# WS2812_MATRIX_7.net
KiCad netlist of a schematic drawn in Altium Designer
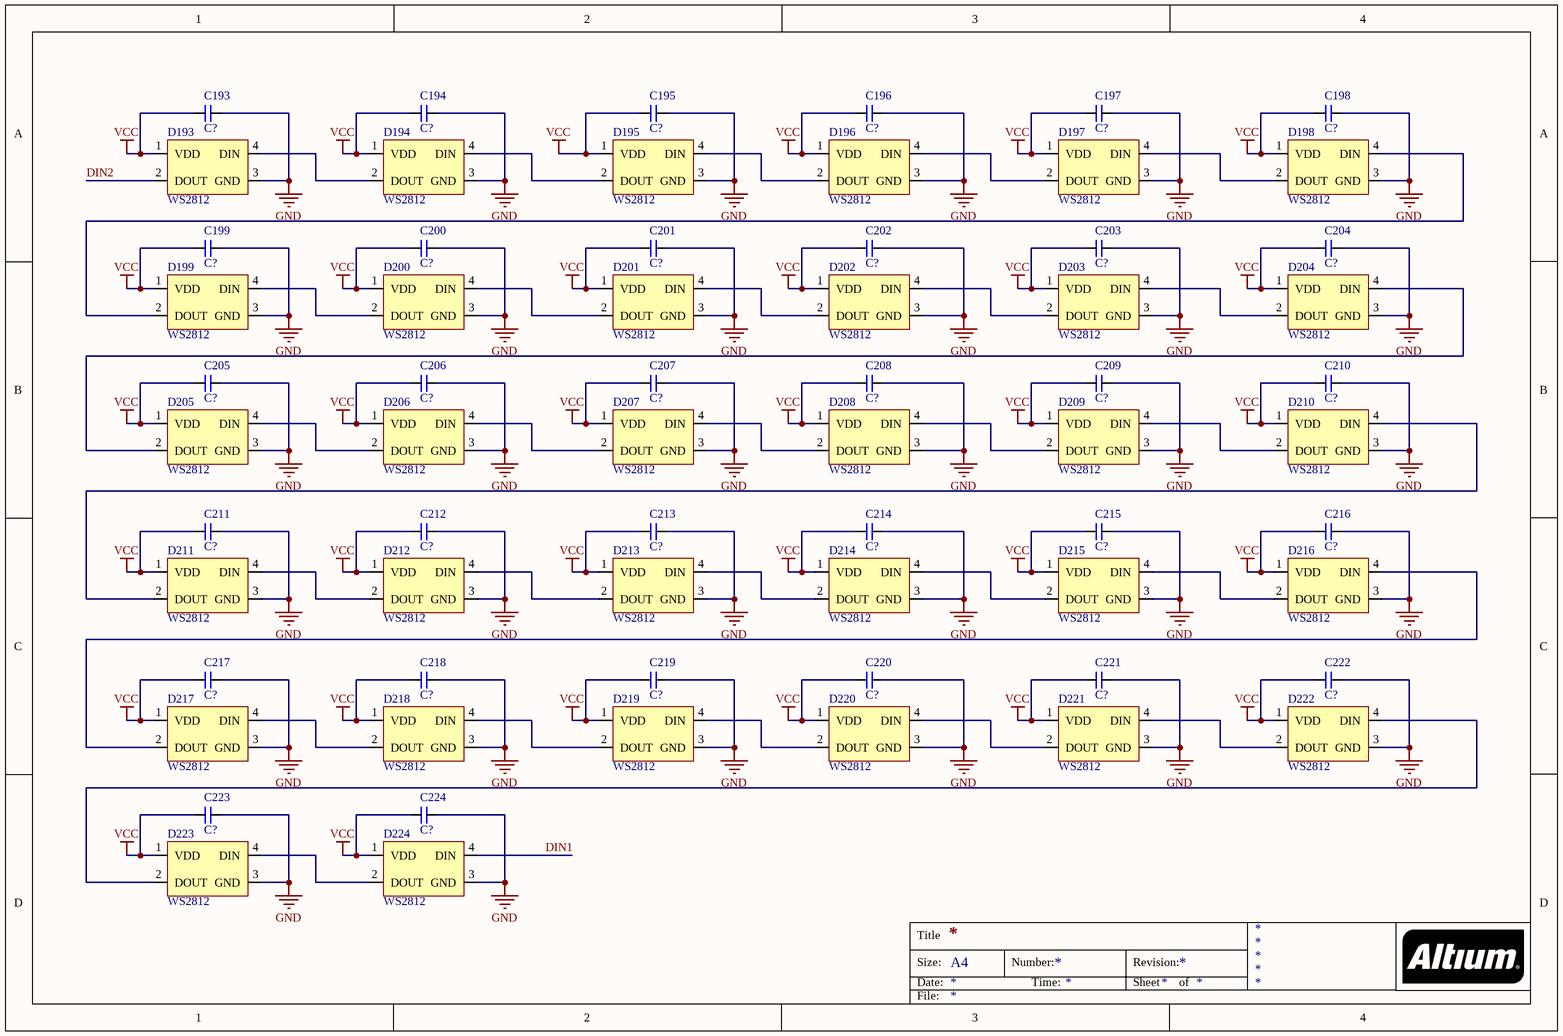
[diagram p0: WS2812_MATRIX_7.SchDoc]

(export (version "E")
  (design (tool "Eeschema 10.0.6"))
  (components
    (comp (ref "C193")
      (value "C?")
      (footprint "C0603")
      (description "Cap")
      (libsource (lib "SCH_Bacsic") (part "CAP"))
    )
    (comp (ref "C194")
      (value "C?")
      (footprint "C0603")
      (description "Cap")
      (libsource (lib "SCH_Bacsic") (part "CAP"))
    )
    (comp (ref "C195")
      (value "C?")
      (footprint "C0603")
      (description "Cap")
      (libsource (lib "SCH_Bacsic") (part "CAP"))
    )
    (comp (ref "C196")
      (value "C?")
      (footprint "C0603")
      (description "Cap")
      (libsource (lib "SCH_Bacsic") (part "CAP"))
    )
    (comp (ref "C197")
      (value "C?")
      (footprint "C0603")
      (description "Cap")
      (libsource (lib "SCH_Bacsic") (part "CAP"))
    )
    (comp (ref "C198")
      (value "C?")
      (footprint "C0603")
      (description "Cap")
      (libsource (lib "SCH_Bacsic") (part "CAP"))
    )
    (comp (ref "C199")
      (value "C?")
      (footprint "C0603")
      (description "Cap")
      (libsource (lib "SCH_Bacsic") (part "CAP"))
    )
    (comp (ref "C200")
      (value "C?")
      (footprint "C0603")
      (description "Cap")
      (libsource (lib "SCH_Bacsic") (part "CAP"))
    )
    (comp (ref "C201")
      (value "C?")
      (footprint "C0603")
      (description "Cap")
      (libsource (lib "SCH_Bacsic") (part "CAP"))
    )
    (comp (ref "C202")
      (value "C?")
      (footprint "C0603")
      (description "Cap")
      (libsource (lib "SCH_Bacsic") (part "CAP"))
    )
    (comp (ref "C203")
      (value "C?")
      (footprint "C0603")
      (description "Cap")
      (libsource (lib "SCH_Bacsic") (part "CAP"))
    )
    (comp (ref "C204")
      (value "C?")
      (footprint "C0603")
      (description "Cap")
      (libsource (lib "SCH_Bacsic") (part "CAP"))
    )
    (comp (ref "C205")
      (value "C?")
      (footprint "C0603")
      (description "Cap")
      (libsource (lib "SCH_Bacsic") (part "CAP"))
    )
    (comp (ref "C206")
      (value "C?")
      (footprint "C0603")
      (description "Cap")
      (libsource (lib "SCH_Bacsic") (part "CAP"))
    )
    (comp (ref "C207")
      (value "C?")
      (footprint "C0603")
      (description "Cap")
      (libsource (lib "SCH_Bacsic") (part "CAP"))
    )
    (comp (ref "C208")
      (value "C?")
      (footprint "C0603")
      (description "Cap")
      (libsource (lib "SCH_Bacsic") (part "CAP"))
    )
    (comp (ref "C209")
      (value "C?")
      (footprint "C0603")
      (description "Cap")
      (libsource (lib "SCH_Bacsic") (part "CAP"))
    )
    (comp (ref "C210")
      (value "C?")
      (footprint "C0603")
      (description "Cap")
      (libsource (lib "SCH_Bacsic") (part "CAP"))
    )
    (comp (ref "C211")
      (value "C?")
      (footprint "C0603")
      (description "Cap")
      (libsource (lib "SCH_Bacsic") (part "CAP"))
    )
    (comp (ref "C212")
      (value "C?")
      (footprint "C0603")
      (description "Cap")
      (libsource (lib "SCH_Bacsic") (part "CAP"))
    )
    (comp (ref "C213")
      (value "C?")
      (footprint "C0603")
      (description "Cap")
      (libsource (lib "SCH_Bacsic") (part "CAP"))
    )
    (comp (ref "C214")
      (value "C?")
      (footprint "C0603")
      (description "Cap")
      (libsource (lib "SCH_Bacsic") (part "CAP"))
    )
    (comp (ref "C215")
      (value "C?")
      (footprint "C0603")
      (description "Cap")
      (libsource (lib "SCH_Bacsic") (part "CAP"))
    )
    (comp (ref "C216")
      (value "C?")
      (footprint "C0603")
      (description "Cap")
      (libsource (lib "SCH_Bacsic") (part "CAP"))
    )
    (comp (ref "C217")
      (value "C?")
      (footprint "C0603")
      (description "Cap")
      (libsource (lib "SCH_Bacsic") (part "CAP"))
    )
    (comp (ref "C218")
      (value "C?")
      (footprint "C0603")
      (description "Cap")
      (libsource (lib "SCH_Bacsic") (part "CAP"))
    )
    (comp (ref "C219")
      (value "C?")
      (footprint "C0603")
      (description "Cap")
      (libsource (lib "SCH_Bacsic") (part "CAP"))
    )
    (comp (ref "C220")
      (value "C?")
      (footprint "C0603")
      (description "Cap")
      (libsource (lib "SCH_Bacsic") (part "CAP"))
    )
    (comp (ref "C221")
      (value "C?")
      (footprint "C0603")
      (description "Cap")
      (libsource (lib "SCH_Bacsic") (part "CAP"))
    )
    (comp (ref "C222")
      (value "C?")
      (footprint "C0603")
      (description "Cap")
      (libsource (lib "SCH_Bacsic") (part "CAP"))
    )
    (comp (ref "C223")
      (value "C?")
      (footprint "C0603")
      (description "Cap")
      (libsource (lib "SCH_Bacsic") (part "CAP"))
    )
    (comp (ref "C224")
      (value "C?")
      (footprint "C0603")
      (description "Cap")
      (libsource (lib "SCH_Bacsic") (part "CAP"))
    )
    (comp (ref "D193")
      (value "WS2812")
      (footprint "WS2812_3528")
      (libsource (lib "SCH_Bacsic") (part "WS2812"))
    )
    (comp (ref "D194")
      (value "WS2812")
      (footprint "WS2812_3528")
      (libsource (lib "SCH_Bacsic") (part "WS2812"))
    )
    (comp (ref "D195")
      (value "WS2812")
      (footprint "WS2812_3528")
      (libsource (lib "SCH_Bacsic") (part "WS2812"))
    )
    (comp (ref "D196")
      (value "WS2812")
      (footprint "WS2812_3528")
      (libsource (lib "SCH_Bacsic") (part "WS2812"))
    )
    (comp (ref "D197")
      (value "WS2812")
      (footprint "WS2812_3528")
      (libsource (lib "SCH_Bacsic") (part "WS2812"))
    )
    (comp (ref "D198")
      (value "WS2812")
      (footprint "WS2812_3528")
      (libsource (lib "SCH_Bacsic") (part "WS2812"))
    )
    (comp (ref "D199")
      (value "WS2812")
      (footprint "WS2812_3528")
      (libsource (lib "SCH_Bacsic") (part "WS2812"))
    )
    (comp (ref "D200")
      (value "WS2812")
      (footprint "WS2812_3528")
      (libsource (lib "SCH_Bacsic") (part "WS2812"))
    )
    (comp (ref "D201")
      (value "WS2812")
      (footprint "WS2812_3528")
      (libsource (lib "SCH_Bacsic") (part "WS2812"))
    )
    (comp (ref "D202")
      (value "WS2812")
      (footprint "WS2812_3528")
      (libsource (lib "SCH_Bacsic") (part "WS2812"))
    )
    (comp (ref "D203")
      (value "WS2812")
      (footprint "WS2812_3528")
      (libsource (lib "SCH_Bacsic") (part "WS2812"))
    )
    (comp (ref "D204")
      (value "WS2812")
      (footprint "WS2812_3528")
      (libsource (lib "SCH_Bacsic") (part "WS2812"))
    )
    (comp (ref "D205")
      (value "WS2812")
      (footprint "WS2812_3528")
      (libsource (lib "SCH_Bacsic") (part "WS2812"))
    )
    (comp (ref "D206")
      (value "WS2812")
      (footprint "WS2812_3528")
      (libsource (lib "SCH_Bacsic") (part "WS2812"))
    )
    (comp (ref "D207")
      (value "WS2812")
      (footprint "WS2812_3528")
      (libsource (lib "SCH_Bacsic") (part "WS2812"))
    )
    (comp (ref "D208")
      (value "WS2812")
      (footprint "WS2812_3528")
      (libsource (lib "SCH_Bacsic") (part "WS2812"))
    )
    (comp (ref "D209")
      (value "WS2812")
      (footprint "WS2812_3528")
      (libsource (lib "SCH_Bacsic") (part "WS2812"))
    )
    (comp (ref "D210")
      (value "WS2812")
      (footprint "WS2812_3528")
      (libsource (lib "SCH_Bacsic") (part "WS2812"))
    )
    (comp (ref "D211")
      (value "WS2812")
      (footprint "WS2812_3528")
      (libsource (lib "SCH_Bacsic") (part "WS2812"))
    )
    (comp (ref "D212")
      (value "WS2812")
      (footprint "WS2812_3528")
      (libsource (lib "SCH_Bacsic") (part "WS2812"))
    )
    (comp (ref "D213")
      (value "WS2812")
      (footprint "WS2812_3528")
      (libsource (lib "SCH_Bacsic") (part "WS2812"))
    )
    (comp (ref "D214")
      (value "WS2812")
      (footprint "WS2812_3528")
      (libsource (lib "SCH_Bacsic") (part "WS2812"))
    )
    (comp (ref "D215")
      (value "WS2812")
      (footprint "WS2812_3528")
      (libsource (lib "SCH_Bacsic") (part "WS2812"))
    )
    (comp (ref "D216")
      (value "WS2812")
      (footprint "WS2812_3528")
      (libsource (lib "SCH_Bacsic") (part "WS2812"))
    )
    (comp (ref "D217")
      (value "WS2812")
      (footprint "WS2812_3528")
      (libsource (lib "SCH_Bacsic") (part "WS2812"))
    )
    (comp (ref "D218")
      (value "WS2812")
      (footprint "WS2812_3528")
      (libsource (lib "SCH_Bacsic") (part "WS2812"))
    )
    (comp (ref "D219")
      (value "WS2812")
      (footprint "WS2812_3528")
      (libsource (lib "SCH_Bacsic") (part "WS2812"))
    )
    (comp (ref "D220")
      (value "WS2812")
      (footprint "WS2812_3528")
      (libsource (lib "SCH_Bacsic") (part "WS2812"))
    )
    (comp (ref "D221")
      (value "WS2812")
      (footprint "WS2812_3528")
      (libsource (lib "SCH_Bacsic") (part "WS2812"))
    )
    (comp (ref "D222")
      (value "WS2812")
      (footprint "WS2812_3528")
      (libsource (lib "SCH_Bacsic") (part "WS2812"))
    )
    (comp (ref "D223")
      (value "WS2812")
      (footprint "WS2812_3528")
      (libsource (lib "SCH_Bacsic") (part "WS2812"))
    )
    (comp (ref "D224")
      (value "WS2812")
      (footprint "WS2812_3528")
      (libsource (lib "SCH_Bacsic") (part "WS2812"))
    )
  )
  (nets
    (net (code "1") (name "/DIN1") (class "Default")
      (node (ref "D224") (pin "4") (pinfunction "DIN_4") (pintype "passive"))
    )
    (net (code "2") (name "/DIN2") (class "Default")
      (node (ref "D193") (pin "2") (pinfunction "DOUT_2") (pintype "passive"))
    )
    (net (code "3") (name "GND") (class "Default")
      (node (ref "C193") (pin "2") (pintype "passive"))
      (node (ref "C194") (pin "2") (pintype "passive"))
      (node (ref "C195") (pin "2") (pintype "passive"))
      (node (ref "C196") (pin "2") (pintype "passive"))
      (node (ref "C197") (pin "2") (pintype "passive"))
      (node (ref "C198") (pin "2") (pintype "passive"))
      (node (ref "C199") (pin "2") (pintype "passive"))
      (node (ref "C200") (pin "2") (pintype "passive"))
      (node (ref "C201") (pin "2") (pintype "passive"))
      (node (ref "C202") (pin "2") (pintype "passive"))
      (node (ref "C203") (pin "2") (pintype "passive"))
      (node (ref "C204") (pin "2") (pintype "passive"))
      (node (ref "C205") (pin "2") (pintype "passive"))
      (node (ref "C206") (pin "2") (pintype "passive"))
      (node (ref "C207") (pin "2") (pintype "passive"))
      (node (ref "C208") (pin "2") (pintype "passive"))
      (node (ref "C209") (pin "2") (pintype "passive"))
      (node (ref "C210") (pin "2") (pintype "passive"))
      (node (ref "C211") (pin "2") (pintype "passive"))
      (node (ref "C212") (pin "2") (pintype "passive"))
      (node (ref "C213") (pin "2") (pintype "passive"))
      (node (ref "C214") (pin "2") (pintype "passive"))
      (node (ref "C215") (pin "2") (pintype "passive"))
      (node (ref "C216") (pin "2") (pintype "passive"))
      (node (ref "C217") (pin "2") (pintype "passive"))
      (node (ref "C218") (pin "2") (pintype "passive"))
      (node (ref "C219") (pin "2") (pintype "passive"))
      (node (ref "C220") (pin "2") (pintype "passive"))
      (node (ref "C221") (pin "2") (pintype "passive"))
      (node (ref "C222") (pin "2") (pintype "passive"))
      (node (ref "C223") (pin "2") (pintype "passive"))
      (node (ref "C224") (pin "2") (pintype "passive"))
      (node (ref "D193") (pin "3") (pinfunction "GND_3") (pintype "passive"))
      (node (ref "D194") (pin "3") (pinfunction "GND_3") (pintype "passive"))
      (node (ref "D195") (pin "3") (pinfunction "GND_3") (pintype "passive"))
      (node (ref "D196") (pin "3") (pinfunction "GND_3") (pintype "passive"))
      (node (ref "D197") (pin "3") (pinfunction "GND_3") (pintype "passive"))
      (node (ref "D198") (pin "3") (pinfunction "GND_3") (pintype "passive"))
      (node (ref "D199") (pin "3") (pinfunction "GND_3") (pintype "passive"))
      (node (ref "D200") (pin "3") (pinfunction "GND_3") (pintype "passive"))
      (node (ref "D201") (pin "3") (pinfunction "GND_3") (pintype "passive"))
      (node (ref "D202") (pin "3") (pinfunction "GND_3") (pintype "passive"))
      (node (ref "D203") (pin "3") (pinfunction "GND_3") (pintype "passive"))
      (node (ref "D204") (pin "3") (pinfunction "GND_3") (pintype "passive"))
      (node (ref "D205") (pin "3") (pinfunction "GND_3") (pintype "passive"))
      (node (ref "D206") (pin "3") (pinfunction "GND_3") (pintype "passive"))
      (node (ref "D207") (pin "3") (pinfunction "GND_3") (pintype "passive"))
      (node (ref "D208") (pin "3") (pinfunction "GND_3") (pintype "passive"))
      (node (ref "D209") (pin "3") (pinfunction "GND_3") (pintype "passive"))
      (node (ref "D210") (pin "3") (pinfunction "GND_3") (pintype "passive"))
      (node (ref "D211") (pin "3") (pinfunction "GND_3") (pintype "passive"))
      (node (ref "D212") (pin "3") (pinfunction "GND_3") (pintype "passive"))
      (node (ref "D213") (pin "3") (pinfunction "GND_3") (pintype "passive"))
      (node (ref "D214") (pin "3") (pinfunction "GND_3") (pintype "passive"))
      (node (ref "D215") (pin "3") (pinfunction "GND_3") (pintype "passive"))
      (node (ref "D216") (pin "3") (pinfunction "GND_3") (pintype "passive"))
      (node (ref "D217") (pin "3") (pinfunction "GND_3") (pintype "passive"))
      (node (ref "D218") (pin "3") (pinfunction "GND_3") (pintype "passive"))
      (node (ref "D219") (pin "3") (pinfunction "GND_3") (pintype "passive"))
      (node (ref "D220") (pin "3") (pinfunction "GND_3") (pintype "passive"))
      (node (ref "D221") (pin "3") (pinfunction "GND_3") (pintype "passive"))
      (node (ref "D222") (pin "3") (pinfunction "GND_3") (pintype "passive"))
      (node (ref "D223") (pin "3") (pinfunction "GND_3") (pintype "passive"))
      (node (ref "D224") (pin "3") (pinfunction "GND_3") (pintype "passive"))
    )
    (net (code "4") (name "Net-(D193-DIN)") (class "Default")
      (node (ref "D193") (pin "4") (pinfunction "DIN_4") (pintype "passive"))
      (node (ref "D194") (pin "2") (pinfunction "DOUT_2") (pintype "passive"))
    )
    (net (code "5") (name "Net-(D194-DIN)") (class "Default")
      (node (ref "D194") (pin "4") (pinfunction "DIN_4") (pintype "passive"))
      (node (ref "D195") (pin "2") (pinfunction "DOUT_2") (pintype "passive"))
    )
    (net (code "6") (name "Net-(D195-DIN)") (class "Default")
      (node (ref "D195") (pin "4") (pinfunction "DIN_4") (pintype "passive"))
      (node (ref "D196") (pin "2") (pinfunction "DOUT_2") (pintype "passive"))
    )
    (net (code "7") (name "Net-(D196-DIN)") (class "Default")
      (node (ref "D196") (pin "4") (pinfunction "DIN_4") (pintype "passive"))
      (node (ref "D197") (pin "2") (pinfunction "DOUT_2") (pintype "passive"))
    )
    (net (code "8") (name "Net-(D197-DIN)") (class "Default")
      (node (ref "D197") (pin "4") (pinfunction "DIN_4") (pintype "passive"))
      (node (ref "D198") (pin "2") (pinfunction "DOUT_2") (pintype "passive"))
    )
    (net (code "9") (name "Net-(D198-DIN)") (class "Default")
      (node (ref "D198") (pin "4") (pinfunction "DIN_4") (pintype "passive"))
      (node (ref "D199") (pin "2") (pinfunction "DOUT_2") (pintype "passive"))
    )
    (net (code "10") (name "Net-(D199-DIN)") (class "Default")
      (node (ref "D199") (pin "4") (pinfunction "DIN_4") (pintype "passive"))
      (node (ref "D200") (pin "2") (pinfunction "DOUT_2") (pintype "passive"))
    )
    (net (code "11") (name "Net-(D200-DIN)") (class "Default")
      (node (ref "D200") (pin "4") (pinfunction "DIN_4") (pintype "passive"))
      (node (ref "D201") (pin "2") (pinfunction "DOUT_2") (pintype "passive"))
    )
    (net (code "12") (name "Net-(D201-DIN)") (class "Default")
      (node (ref "D201") (pin "4") (pinfunction "DIN_4") (pintype "passive"))
      (node (ref "D202") (pin "2") (pinfunction "DOUT_2") (pintype "passive"))
    )
    (net (code "13") (name "Net-(D202-DIN)") (class "Default")
      (node (ref "D202") (pin "4") (pinfunction "DIN_4") (pintype "passive"))
      (node (ref "D203") (pin "2") (pinfunction "DOUT_2") (pintype "passive"))
    )
    (net (code "14") (name "Net-(D203-DIN)") (class "Default")
      (node (ref "D203") (pin "4") (pinfunction "DIN_4") (pintype "passive"))
      (node (ref "D204") (pin "2") (pinfunction "DOUT_2") (pintype "passive"))
    )
    (net (code "15") (name "Net-(D204-DIN)") (class "Default")
      (node (ref "D204") (pin "4") (pinfunction "DIN_4") (pintype "passive"))
      (node (ref "D205") (pin "2") (pinfunction "DOUT_2") (pintype "passive"))
    )
    (net (code "16") (name "Net-(D205-DIN)") (class "Default")
      (node (ref "D205") (pin "4") (pinfunction "DIN_4") (pintype "passive"))
      (node (ref "D206") (pin "2") (pinfunction "DOUT_2") (pintype "passive"))
    )
    (net (code "17") (name "Net-(D206-DIN)") (class "Default")
      (node (ref "D206") (pin "4") (pinfunction "DIN_4") (pintype "passive"))
      (node (ref "D207") (pin "2") (pinfunction "DOUT_2") (pintype "passive"))
    )
    (net (code "18") (name "Net-(D207-DIN)") (class "Default")
      (node (ref "D207") (pin "4") (pinfunction "DIN_4") (pintype "passive"))
      (node (ref "D208") (pin "2") (pinfunction "DOUT_2") (pintype "passive"))
    )
    (net (code "19") (name "Net-(D208-DIN)") (class "Default")
      (node (ref "D208") (pin "4") (pinfunction "DIN_4") (pintype "passive"))
      (node (ref "D209") (pin "2") (pinfunction "DOUT_2") (pintype "passive"))
    )
    (net (code "20") (name "Net-(D209-DIN)") (class "Default")
      (node (ref "D209") (pin "4") (pinfunction "DIN_4") (pintype "passive"))
      (node (ref "D210") (pin "2") (pinfunction "DOUT_2") (pintype "passive"))
    )
    (net (code "21") (name "Net-(D210-DIN)") (class "Default")
      (node (ref "D210") (pin "4") (pinfunction "DIN_4") (pintype "passive"))
      (node (ref "D211") (pin "2") (pinfunction "DOUT_2") (pintype "passive"))
    )
    (net (code "22") (name "Net-(D211-DIN)") (class "Default")
      (node (ref "D211") (pin "4") (pinfunction "DIN_4") (pintype "passive"))
      (node (ref "D212") (pin "2") (pinfunction "DOUT_2") (pintype "passive"))
    )
    (net (code "23") (name "Net-(D212-DIN)") (class "Default")
      (node (ref "D212") (pin "4") (pinfunction "DIN_4") (pintype "passive"))
      (node (ref "D213") (pin "2") (pinfunction "DOUT_2") (pintype "passive"))
    )
    (net (code "24") (name "Net-(D213-DIN)") (class "Default")
      (node (ref "D213") (pin "4") (pinfunction "DIN_4") (pintype "passive"))
      (node (ref "D214") (pin "2") (pinfunction "DOUT_2") (pintype "passive"))
    )
    (net (code "25") (name "Net-(D214-DIN)") (class "Default")
      (node (ref "D214") (pin "4") (pinfunction "DIN_4") (pintype "passive"))
      (node (ref "D215") (pin "2") (pinfunction "DOUT_2") (pintype "passive"))
    )
    (net (code "26") (name "Net-(D215-DIN)") (class "Default")
      (node (ref "D215") (pin "4") (pinfunction "DIN_4") (pintype "passive"))
      (node (ref "D216") (pin "2") (pinfunction "DOUT_2") (pintype "passive"))
    )
    (net (code "27") (name "Net-(D216-DIN)") (class "Default")
      (node (ref "D216") (pin "4") (pinfunction "DIN_4") (pintype "passive"))
      (node (ref "D217") (pin "2") (pinfunction "DOUT_2") (pintype "passive"))
    )
    (net (code "28") (name "Net-(D217-DIN)") (class "Default")
      (node (ref "D217") (pin "4") (pinfunction "DIN_4") (pintype "passive"))
      (node (ref "D218") (pin "2") (pinfunction "DOUT_2") (pintype "passive"))
    )
    (net (code "29") (name "Net-(D218-DIN)") (class "Default")
      (node (ref "D218") (pin "4") (pinfunction "DIN_4") (pintype "passive"))
      (node (ref "D219") (pin "2") (pinfunction "DOUT_2") (pintype "passive"))
    )
    (net (code "30") (name "Net-(D219-DIN)") (class "Default")
      (node (ref "D219") (pin "4") (pinfunction "DIN_4") (pintype "passive"))
      (node (ref "D220") (pin "2") (pinfunction "DOUT_2") (pintype "passive"))
    )
    (net (code "31") (name "Net-(D220-DIN)") (class "Default")
      (node (ref "D220") (pin "4") (pinfunction "DIN_4") (pintype "passive"))
      (node (ref "D221") (pin "2") (pinfunction "DOUT_2") (pintype "passive"))
    )
    (net (code "32") (name "Net-(D221-DIN)") (class "Default")
      (node (ref "D221") (pin "4") (pinfunction "DIN_4") (pintype "passive"))
      (node (ref "D222") (pin "2") (pinfunction "DOUT_2") (pintype "passive"))
    )
    (net (code "33") (name "Net-(D222-DIN)") (class "Default")
      (node (ref "D222") (pin "4") (pinfunction "DIN_4") (pintype "passive"))
      (node (ref "D223") (pin "2") (pinfunction "DOUT_2") (pintype "passive"))
    )
    (net (code "34") (name "Net-(D223-DIN)") (class "Default")
      (node (ref "D223") (pin "4") (pinfunction "DIN_4") (pintype "passive"))
      (node (ref "D224") (pin "2") (pinfunction "DOUT_2") (pintype "passive"))
    )
    (net (code "35") (name "VCC") (class "Default")
      (node (ref "C193") (pin "1") (pintype "passive"))
      (node (ref "C194") (pin "1") (pintype "passive"))
      (node (ref "C195") (pin "1") (pintype "passive"))
      (node (ref "C196") (pin "1") (pintype "passive"))
      (node (ref "C197") (pin "1") (pintype "passive"))
      (node (ref "C198") (pin "1") (pintype "passive"))
      (node (ref "C199") (pin "1") (pintype "passive"))
      (node (ref "C200") (pin "1") (pintype "passive"))
      (node (ref "C201") (pin "1") (pintype "passive"))
      (node (ref "C202") (pin "1") (pintype "passive"))
      (node (ref "C203") (pin "1") (pintype "passive"))
      (node (ref "C204") (pin "1") (pintype "passive"))
      (node (ref "C205") (pin "1") (pintype "passive"))
      (node (ref "C206") (pin "1") (pintype "passive"))
      (node (ref "C207") (pin "1") (pintype "passive"))
      (node (ref "C208") (pin "1") (pintype "passive"))
      (node (ref "C209") (pin "1") (pintype "passive"))
      (node (ref "C210") (pin "1") (pintype "passive"))
      (node (ref "C211") (pin "1") (pintype "passive"))
      (node (ref "C212") (pin "1") (pintype "passive"))
      (node (ref "C213") (pin "1") (pintype "passive"))
      (node (ref "C214") (pin "1") (pintype "passive"))
      (node (ref "C215") (pin "1") (pintype "passive"))
      (node (ref "C216") (pin "1") (pintype "passive"))
      (node (ref "C217") (pin "1") (pintype "passive"))
      (node (ref "C218") (pin "1") (pintype "passive"))
      (node (ref "C219") (pin "1") (pintype "passive"))
      (node (ref "C220") (pin "1") (pintype "passive"))
      (node (ref "C221") (pin "1") (pintype "passive"))
      (node (ref "C222") (pin "1") (pintype "passive"))
      (node (ref "C223") (pin "1") (pintype "passive"))
      (node (ref "C224") (pin "1") (pintype "passive"))
      (node (ref "D193") (pin "1") (pinfunction "VDD_1") (pintype "passive"))
      (node (ref "D194") (pin "1") (pinfunction "VDD_1") (pintype "passive"))
      (node (ref "D195") (pin "1") (pinfunction "VDD_1") (pintype "passive"))
      (node (ref "D196") (pin "1") (pinfunction "VDD_1") (pintype "passive"))
      (node (ref "D197") (pin "1") (pinfunction "VDD_1") (pintype "passive"))
      (node (ref "D198") (pin "1") (pinfunction "VDD_1") (pintype "passive"))
      (node (ref "D199") (pin "1") (pinfunction "VDD_1") (pintype "passive"))
      (node (ref "D200") (pin "1") (pinfunction "VDD_1") (pintype "passive"))
      (node (ref "D201") (pin "1") (pinfunction "VDD_1") (pintype "passive"))
      (node (ref "D202") (pin "1") (pinfunction "VDD_1") (pintype "passive"))
      (node (ref "D203") (pin "1") (pinfunction "VDD_1") (pintype "passive"))
      (node (ref "D204") (pin "1") (pinfunction "VDD_1") (pintype "passive"))
      (node (ref "D205") (pin "1") (pinfunction "VDD_1") (pintype "passive"))
      (node (ref "D206") (pin "1") (pinfunction "VDD_1") (pintype "passive"))
      (node (ref "D207") (pin "1") (pinfunction "VDD_1") (pintype "passive"))
      (node (ref "D208") (pin "1") (pinfunction "VDD_1") (pintype "passive"))
      (node (ref "D209") (pin "1") (pinfunction "VDD_1") (pintype "passive"))
      (node (ref "D210") (pin "1") (pinfunction "VDD_1") (pintype "passive"))
      (node (ref "D211") (pin "1") (pinfunction "VDD_1") (pintype "passive"))
      (node (ref "D212") (pin "1") (pinfunction "VDD_1") (pintype "passive"))
      (node (ref "D213") (pin "1") (pinfunction "VDD_1") (pintype "passive"))
      (node (ref "D214") (pin "1") (pinfunction "VDD_1") (pintype "passive"))
      (node (ref "D215") (pin "1") (pinfunction "VDD_1") (pintype "passive"))
      (node (ref "D216") (pin "1") (pinfunction "VDD_1") (pintype "passive"))
      (node (ref "D217") (pin "1") (pinfunction "VDD_1") (pintype "passive"))
      (node (ref "D218") (pin "1") (pinfunction "VDD_1") (pintype "passive"))
      (node (ref "D219") (pin "1") (pinfunction "VDD_1") (pintype "passive"))
      (node (ref "D220") (pin "1") (pinfunction "VDD_1") (pintype "passive"))
      (node (ref "D221") (pin "1") (pinfunction "VDD_1") (pintype "passive"))
      (node (ref "D222") (pin "1") (pinfunction "VDD_1") (pintype "passive"))
      (node (ref "D223") (pin "1") (pinfunction "VDD_1") (pintype "passive"))
      (node (ref "D224") (pin "1") (pinfunction "VDD_1") (pintype "passive"))
    )
  )
)
